# famicom_bootleg_cart_edge_v2.net
KiCad netlist of a schematic drawn in EAGLE
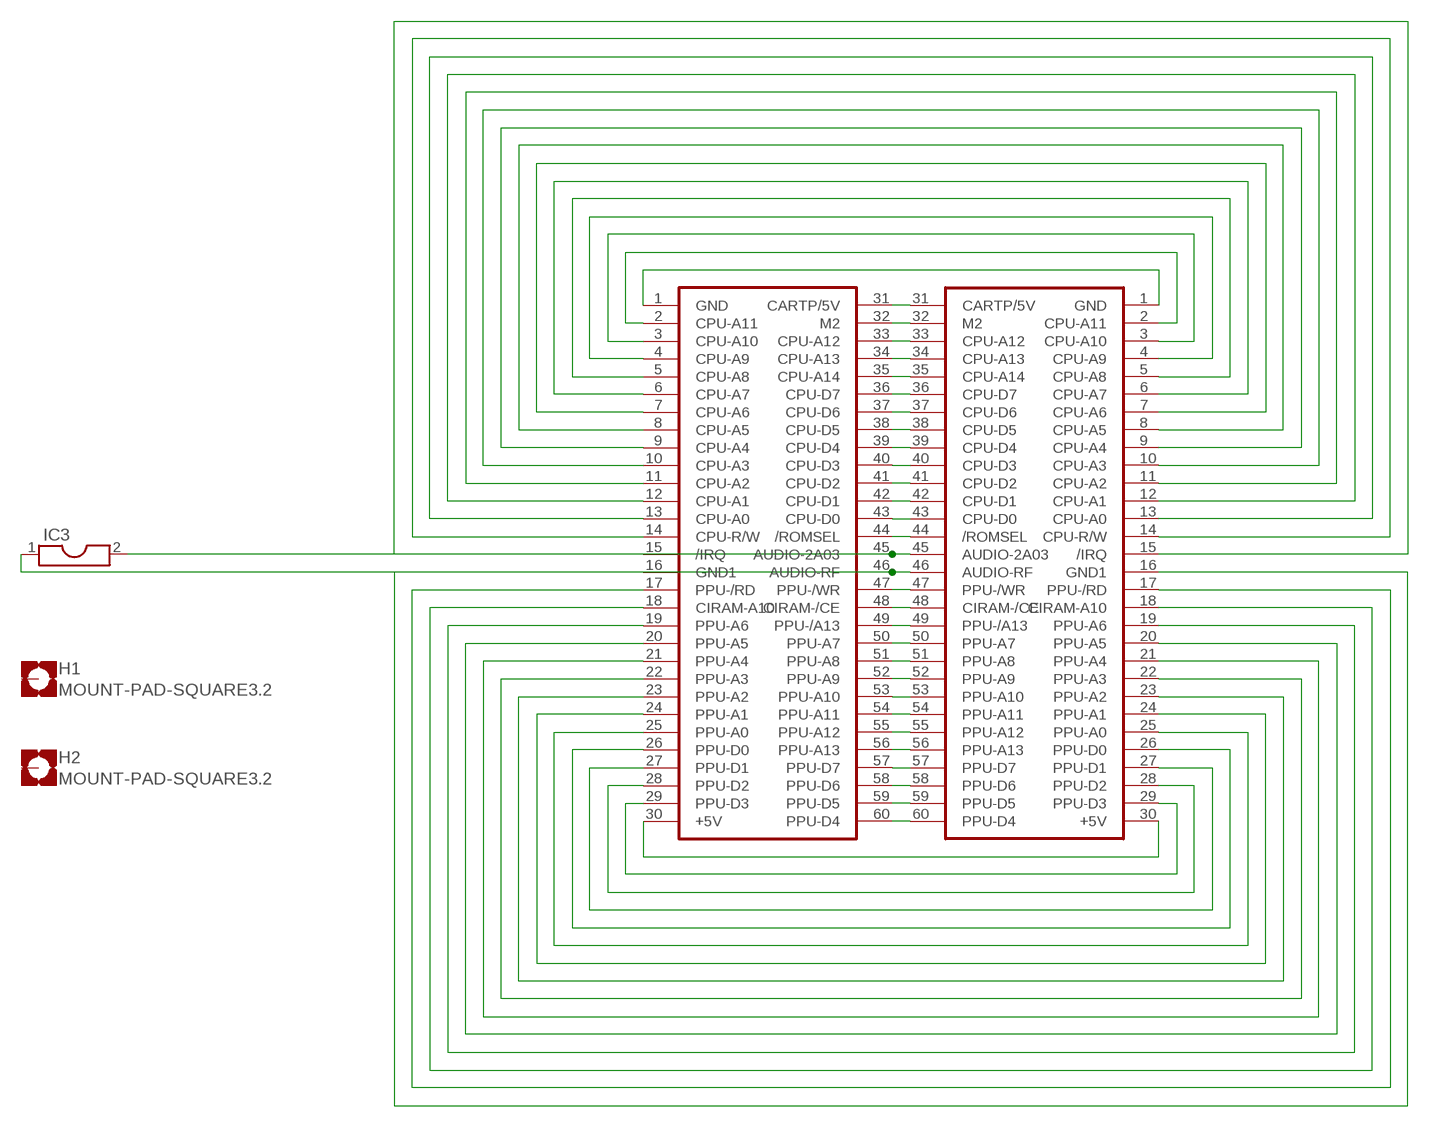
[diagram p0: schematic, sheet 1]

(export (version "E")
  (design (tool "Eeschema 10.0.6"))
  (components
    (comp (ref "H1")
      (value "MOUNT-PAD-SQUARE3.2")
      (footprint "eagle-import:3,2-PAD-SQUARE")
      (libsource (lib "eagle-import") (part "MOUNT-PAD-SQUARE3.2"))
    )
    (comp (ref "H2")
      (value "MOUNT-PAD-SQUARE3.2")
      (footprint "eagle-import:3,2-PAD-SQUARE")
      (libsource (lib "eagle-import") (part "MOUNT-PAD-SQUARE3.2"))
    )
    (comp (ref "IC1")
      (value "FAMICOM-CART-EDGE")
      (footprint "eagle-import:DIL60")
      (libsource (lib "eagle-import") (part "FAMICOM-CART-EDGE"))
    )
    (comp (ref "IC2")
      (value "FAMICOM-CART-EDGE")
      (footprint "eagle-import:DIL60")
      (libsource (lib "eagle-import") (part "FAMICOM-CART-EDGE"))
    )
    (comp (ref "IC3")
      (value "DIL2")
      (footprint "eagle-import:DIL02")
      (libsource (lib "eagle-import") (part "DIL2"))
    )
  )
  (nets
    (net (code "1") (name "Net-(IC1-+5V)") (class "Default")
      (node (ref "IC1") (pin "30") (pinfunction "+5V_30") (pintype "input"))
      (node (ref "IC2") (pin "30") (pinfunction "+5V_30") (pintype "input"))
    )
    (net (code "2") (name "Net-(IC1-AUDIO-2A03)") (class "Default")
      (node (ref "IC1") (pin "45") (pinfunction "AUDIO-2A03_45") (pintype "open_collector"))
      (node (ref "IC2") (pin "45") (pinfunction "AUDIO-2A03_45") (pintype "open_collector"))
      (node (ref "IC3") (pin "2") (pinfunction "2_2") (pintype "passive"))
    )
    (net (code "3") (name "Net-(IC1-AUDIO-RF)") (class "Default")
      (node (ref "IC1") (pin "46") (pinfunction "AUDIO-RF_46") (pintype "open_collector"))
      (node (ref "IC2") (pin "46") (pinfunction "AUDIO-RF_46") (pintype "open_collector"))
      (node (ref "IC3") (pin "1") (pinfunction "1_1") (pintype "passive"))
    )
    (net (code "4") (name "Net-(IC1-CARTP{slash}5V)") (class "Default")
      (node (ref "IC1") (pin "31") (pinfunction "CARTP/5V_31") (pintype "open_collector"))
      (node (ref "IC2") (pin "31") (pinfunction "CARTP/5V_31") (pintype "open_collector"))
    )
    (net (code "5") (name "Net-(IC1-CIRAM-A10)") (class "Default")
      (node (ref "IC1") (pin "18") (pinfunction "CIRAM-A10_18") (pintype "input"))
      (node (ref "IC2") (pin "18") (pinfunction "CIRAM-A10_18") (pintype "input"))
    )
    (net (code "6") (name "Net-(IC1-CIRAM-{slash}CE)") (class "Default")
      (node (ref "IC1") (pin "48") (pinfunction "CIRAM-/CE_48") (pintype "open_collector"))
      (node (ref "IC2") (pin "48") (pinfunction "CIRAM-/CE_48") (pintype "open_collector"))
    )
    (net (code "7") (name "Net-(IC1-CPU-A0)") (class "Default")
      (node (ref "IC1") (pin "13") (pinfunction "CPU-A0_13") (pintype "input"))
      (node (ref "IC2") (pin "13") (pinfunction "CPU-A0_13") (pintype "input"))
    )
    (net (code "8") (name "Net-(IC1-CPU-A1)") (class "Default")
      (node (ref "IC1") (pin "12") (pinfunction "CPU-A1_12") (pintype "input"))
      (node (ref "IC2") (pin "12") (pinfunction "CPU-A1_12") (pintype "input"))
    )
    (net (code "9") (name "Net-(IC1-CPU-A2)") (class "Default")
      (node (ref "IC1") (pin "11") (pinfunction "CPU-A2_11") (pintype "input"))
      (node (ref "IC2") (pin "11") (pinfunction "CPU-A2_11") (pintype "input"))
    )
    (net (code "10") (name "Net-(IC1-CPU-A3)") (class "Default")
      (node (ref "IC1") (pin "10") (pinfunction "CPU-A3_10") (pintype "input"))
      (node (ref "IC2") (pin "10") (pinfunction "CPU-A3_10") (pintype "input"))
    )
    (net (code "11") (name "Net-(IC1-CPU-A4)") (class "Default")
      (node (ref "IC1") (pin "9") (pinfunction "CPU-A4_9") (pintype "input"))
      (node (ref "IC2") (pin "9") (pinfunction "CPU-A4_9") (pintype "input"))
    )
    (net (code "12") (name "Net-(IC1-CPU-A5)") (class "Default")
      (node (ref "IC1") (pin "8") (pinfunction "CPU-A5_8") (pintype "input"))
      (node (ref "IC2") (pin "8") (pinfunction "CPU-A5_8") (pintype "input"))
    )
    (net (code "13") (name "Net-(IC1-CPU-A6)") (class "Default")
      (node (ref "IC1") (pin "7") (pinfunction "CPU-A6_7") (pintype "input"))
      (node (ref "IC2") (pin "7") (pinfunction "CPU-A6_7") (pintype "input"))
    )
    (net (code "14") (name "Net-(IC1-CPU-A7)") (class "Default")
      (node (ref "IC1") (pin "6") (pinfunction "CPU-A7_6") (pintype "input"))
      (node (ref "IC2") (pin "6") (pinfunction "CPU-A7_6") (pintype "input"))
    )
    (net (code "15") (name "Net-(IC1-CPU-A8)") (class "Default")
      (node (ref "IC1") (pin "5") (pinfunction "CPU-A8_5") (pintype "input"))
      (node (ref "IC2") (pin "5") (pinfunction "CPU-A8_5") (pintype "input"))
    )
    (net (code "16") (name "Net-(IC1-CPU-A9)") (class "Default")
      (node (ref "IC1") (pin "4") (pinfunction "CPU-A9_4") (pintype "input"))
      (node (ref "IC2") (pin "4") (pinfunction "CPU-A9_4") (pintype "input"))
    )
    (net (code "17") (name "Net-(IC1-CPU-A10)") (class "Default")
      (node (ref "IC1") (pin "3") (pinfunction "CPU-A10_3") (pintype "input"))
      (node (ref "IC2") (pin "3") (pinfunction "CPU-A10_3") (pintype "input"))
    )
    (net (code "18") (name "Net-(IC1-CPU-A11)") (class "Default")
      (node (ref "IC1") (pin "2") (pinfunction "CPU-A11_2") (pintype "input"))
      (node (ref "IC2") (pin "2") (pinfunction "CPU-A11_2") (pintype "input"))
    )
    (net (code "19") (name "Net-(IC1-CPU-A12)") (class "Default")
      (node (ref "IC1") (pin "33") (pinfunction "CPU-A12_33") (pintype "open_collector"))
      (node (ref "IC2") (pin "33") (pinfunction "CPU-A12_33") (pintype "open_collector"))
    )
    (net (code "20") (name "Net-(IC1-CPU-A13)") (class "Default")
      (node (ref "IC1") (pin "34") (pinfunction "CPU-A13_34") (pintype "open_collector"))
      (node (ref "IC2") (pin "34") (pinfunction "CPU-A13_34") (pintype "open_collector"))
    )
    (net (code "21") (name "Net-(IC1-CPU-A14)") (class "Default")
      (node (ref "IC1") (pin "35") (pinfunction "CPU-A14_35") (pintype "open_collector"))
      (node (ref "IC2") (pin "35") (pinfunction "CPU-A14_35") (pintype "open_collector"))
    )
    (net (code "22") (name "Net-(IC1-CPU-D0)") (class "Default")
      (node (ref "IC1") (pin "43") (pinfunction "CPU-D0_43") (pintype "open_collector"))
      (node (ref "IC2") (pin "43") (pinfunction "CPU-D0_43") (pintype "open_collector"))
    )
    (net (code "23") (name "Net-(IC1-CPU-D1)") (class "Default")
      (node (ref "IC1") (pin "42") (pinfunction "CPU-D1_42") (pintype "open_collector"))
      (node (ref "IC2") (pin "42") (pinfunction "CPU-D1_42") (pintype "open_collector"))
    )
    (net (code "24") (name "Net-(IC1-CPU-D2)") (class "Default")
      (node (ref "IC1") (pin "41") (pinfunction "CPU-D2_41") (pintype "open_collector"))
      (node (ref "IC2") (pin "41") (pinfunction "CPU-D2_41") (pintype "open_collector"))
    )
    (net (code "25") (name "Net-(IC1-CPU-D3)") (class "Default")
      (node (ref "IC1") (pin "40") (pinfunction "CPU-D3_40") (pintype "open_collector"))
      (node (ref "IC2") (pin "40") (pinfunction "CPU-D3_40") (pintype "open_collector"))
    )
    (net (code "26") (name "Net-(IC1-CPU-D4)") (class "Default")
      (node (ref "IC1") (pin "39") (pinfunction "CPU-D4_39") (pintype "open_collector"))
      (node (ref "IC2") (pin "39") (pinfunction "CPU-D4_39") (pintype "open_collector"))
    )
    (net (code "27") (name "Net-(IC1-CPU-D5)") (class "Default")
      (node (ref "IC1") (pin "38") (pinfunction "CPU-D5_38") (pintype "open_collector"))
      (node (ref "IC2") (pin "38") (pinfunction "CPU-D5_38") (pintype "open_collector"))
    )
    (net (code "28") (name "Net-(IC1-CPU-D6)") (class "Default")
      (node (ref "IC1") (pin "37") (pinfunction "CPU-D6_37") (pintype "open_collector"))
      (node (ref "IC2") (pin "37") (pinfunction "CPU-D6_37") (pintype "open_collector"))
    )
    (net (code "29") (name "Net-(IC1-CPU-D7)") (class "Default")
      (node (ref "IC1") (pin "36") (pinfunction "CPU-D7_36") (pintype "open_collector"))
      (node (ref "IC2") (pin "36") (pinfunction "CPU-D7_36") (pintype "open_collector"))
    )
    (net (code "30") (name "Net-(IC1-CPU-R{slash}W)") (class "Default")
      (node (ref "IC1") (pin "14") (pinfunction "CPU-R/W_14") (pintype "input"))
      (node (ref "IC2") (pin "14") (pinfunction "CPU-R/W_14") (pintype "input"))
    )
    (net (code "31") (name "Net-(IC1-GND)") (class "Default")
      (node (ref "IC1") (pin "1") (pinfunction "GND_1") (pintype "input"))
      (node (ref "IC2") (pin "1") (pinfunction "GND_1") (pintype "input"))
    )
    (net (code "32") (name "Net-(IC1-GND1)") (class "Default")
      (node (ref "IC1") (pin "16") (pinfunction "GND1_16") (pintype "input"))
      (node (ref "IC2") (pin "16") (pinfunction "GND1_16") (pintype "input"))
    )
    (net (code "33") (name "Net-(IC1-M2)") (class "Default")
      (node (ref "IC1") (pin "32") (pinfunction "M2_32") (pintype "open_collector"))
      (node (ref "IC2") (pin "32") (pinfunction "M2_32") (pintype "open_collector"))
    )
    (net (code "34") (name "Net-(IC1-PPU-A0)") (class "Default")
      (node (ref "IC1") (pin "25") (pinfunction "PPU-A0_25") (pintype "input"))
      (node (ref "IC2") (pin "25") (pinfunction "PPU-A0_25") (pintype "input"))
    )
    (net (code "35") (name "Net-(IC1-PPU-A1)") (class "Default")
      (node (ref "IC1") (pin "24") (pinfunction "PPU-A1_24") (pintype "input"))
      (node (ref "IC2") (pin "24") (pinfunction "PPU-A1_24") (pintype "input"))
    )
    (net (code "36") (name "Net-(IC1-PPU-A2)") (class "Default")
      (node (ref "IC1") (pin "23") (pinfunction "PPU-A2_23") (pintype "input"))
      (node (ref "IC2") (pin "23") (pinfunction "PPU-A2_23") (pintype "input"))
    )
    (net (code "37") (name "Net-(IC1-PPU-A3)") (class "Default")
      (node (ref "IC1") (pin "22") (pinfunction "PPU-A3_22") (pintype "input"))
      (node (ref "IC2") (pin "22") (pinfunction "PPU-A3_22") (pintype "input"))
    )
    (net (code "38") (name "Net-(IC1-PPU-A4)") (class "Default")
      (node (ref "IC1") (pin "21") (pinfunction "PPU-A4_21") (pintype "input"))
      (node (ref "IC2") (pin "21") (pinfunction "PPU-A4_21") (pintype "input"))
    )
    (net (code "39") (name "Net-(IC1-PPU-A5)") (class "Default")
      (node (ref "IC1") (pin "20") (pinfunction "PPU-A5_20") (pintype "input"))
      (node (ref "IC2") (pin "20") (pinfunction "PPU-A5_20") (pintype "input"))
    )
    (net (code "40") (name "Net-(IC1-PPU-A6)") (class "Default")
      (node (ref "IC1") (pin "19") (pinfunction "PPU-A6_19") (pintype "input"))
      (node (ref "IC2") (pin "19") (pinfunction "PPU-A6_19") (pintype "input"))
    )
    (net (code "41") (name "Net-(IC1-PPU-A7)") (class "Default")
      (node (ref "IC1") (pin "50") (pinfunction "PPU-A7_50") (pintype "input"))
      (node (ref "IC2") (pin "50") (pinfunction "PPU-A7_50") (pintype "input"))
    )
    (net (code "42") (name "Net-(IC1-PPU-A8)") (class "Default")
      (node (ref "IC1") (pin "51") (pinfunction "PPU-A8_51") (pintype "input"))
      (node (ref "IC2") (pin "51") (pinfunction "PPU-A8_51") (pintype "input"))
    )
    (net (code "43") (name "Net-(IC1-PPU-A9)") (class "Default")
      (node (ref "IC1") (pin "52") (pinfunction "PPU-A9_52") (pintype "input"))
      (node (ref "IC2") (pin "52") (pinfunction "PPU-A9_52") (pintype "input"))
    )
    (net (code "44") (name "Net-(IC1-PPU-A10)") (class "Default")
      (node (ref "IC1") (pin "53") (pinfunction "PPU-A10_53") (pintype "input"))
      (node (ref "IC2") (pin "53") (pinfunction "PPU-A10_53") (pintype "input"))
    )
    (net (code "45") (name "Net-(IC1-PPU-A11)") (class "Default")
      (node (ref "IC1") (pin "54") (pinfunction "PPU-A11_54") (pintype "input"))
      (node (ref "IC2") (pin "54") (pinfunction "PPU-A11_54") (pintype "input"))
    )
    (net (code "46") (name "Net-(IC1-PPU-A12)") (class "Default")
      (node (ref "IC1") (pin "55") (pinfunction "PPU-A12_55") (pintype "input"))
      (node (ref "IC2") (pin "55") (pinfunction "PPU-A12_55") (pintype "input"))
    )
    (net (code "47") (name "Net-(IC1-PPU-A13)") (class "Default")
      (node (ref "IC1") (pin "56") (pinfunction "PPU-A13_56") (pintype "input"))
      (node (ref "IC2") (pin "56") (pinfunction "PPU-A13_56") (pintype "input"))
    )
    (net (code "48") (name "Net-(IC1-PPU-D0)") (class "Default")
      (node (ref "IC1") (pin "26") (pinfunction "PPU-D0_26") (pintype "input"))
      (node (ref "IC2") (pin "26") (pinfunction "PPU-D0_26") (pintype "input"))
    )
    (net (code "49") (name "Net-(IC1-PPU-D1)") (class "Default")
      (node (ref "IC1") (pin "27") (pinfunction "PPU-D1_27") (pintype "input"))
      (node (ref "IC2") (pin "27") (pinfunction "PPU-D1_27") (pintype "input"))
    )
    (net (code "50") (name "Net-(IC1-PPU-D2)") (class "Default")
      (node (ref "IC1") (pin "28") (pinfunction "PPU-D2_28") (pintype "input"))
      (node (ref "IC2") (pin "28") (pinfunction "PPU-D2_28") (pintype "input"))
    )
    (net (code "51") (name "Net-(IC1-PPU-D3)") (class "Default")
      (node (ref "IC1") (pin "29") (pinfunction "PPU-D3_29") (pintype "input"))
      (node (ref "IC2") (pin "29") (pinfunction "PPU-D3_29") (pintype "input"))
    )
    (net (code "52") (name "Net-(IC1-PPU-D4)") (class "Default")
      (node (ref "IC1") (pin "60") (pinfunction "PPU-D4_60") (pintype "input"))
      (node (ref "IC2") (pin "60") (pinfunction "PPU-D4_60") (pintype "input"))
    )
    (net (code "53") (name "Net-(IC1-PPU-D5)") (class "Default")
      (node (ref "IC1") (pin "59") (pinfunction "PPU-D5_59") (pintype "input"))
      (node (ref "IC2") (pin "59") (pinfunction "PPU-D5_59") (pintype "input"))
    )
    (net (code "54") (name "Net-(IC1-PPU-D6)") (class "Default")
      (node (ref "IC1") (pin "58") (pinfunction "PPU-D6_58") (pintype "input"))
      (node (ref "IC2") (pin "58") (pinfunction "PPU-D6_58") (pintype "input"))
    )
    (net (code "55") (name "Net-(IC1-PPU-D7)") (class "Default")
      (node (ref "IC1") (pin "57") (pinfunction "PPU-D7_57") (pintype "input"))
      (node (ref "IC2") (pin "57") (pinfunction "PPU-D7_57") (pintype "input"))
    )
    (net (code "56") (name "Net-(IC1-PPU-{slash}A13)") (class "Default")
      (node (ref "IC1") (pin "49") (pinfunction "PPU-/A13_49") (pintype "input"))
      (node (ref "IC2") (pin "49") (pinfunction "PPU-/A13_49") (pintype "input"))
    )
    (net (code "57") (name "Net-(IC1-PPU-{slash}RD)") (class "Default")
      (node (ref "IC1") (pin "17") (pinfunction "PPU-/RD_17") (pintype "input"))
      (node (ref "IC2") (pin "17") (pinfunction "PPU-/RD_17") (pintype "input"))
    )
    (net (code "58") (name "Net-(IC1-PPU-{slash}WR)") (class "Default")
      (node (ref "IC1") (pin "47") (pinfunction "PPU-/WR_47") (pintype "open_collector"))
      (node (ref "IC2") (pin "47") (pinfunction "PPU-/WR_47") (pintype "open_collector"))
    )
    (net (code "59") (name "Net-(IC1-{slash}IRQ)") (class "Default")
      (node (ref "IC1") (pin "15") (pinfunction "/IRQ_15") (pintype "input"))
      (node (ref "IC2") (pin "15") (pinfunction "/IRQ_15") (pintype "input"))
    )
    (net (code "60") (name "Net-(IC1-{slash}ROMSEL)") (class "Default")
      (node (ref "IC1") (pin "44") (pinfunction "/ROMSEL_44") (pintype "open_collector"))
      (node (ref "IC2") (pin "44") (pinfunction "/ROMSEL_44") (pintype "open_collector"))
    )
    (net (code "61") (name "unconnected-(H1-MOUNT-PadB3,2)") (class "Default")
      (node (ref "H1") (pin "B3,2") (pinfunction "MOUNT_B3,2") (pintype "passive"))
    )
    (net (code "62") (name "unconnected-(H2-MOUNT-PadB3,2)") (class "Default")
      (node (ref "H2") (pin "B3,2") (pinfunction "MOUNT_B3,2") (pintype "passive"))
    )
  )
)
